# 24_-_HEADERS_UART.net
KiCad netlist of a schematic drawn in Altium Designer
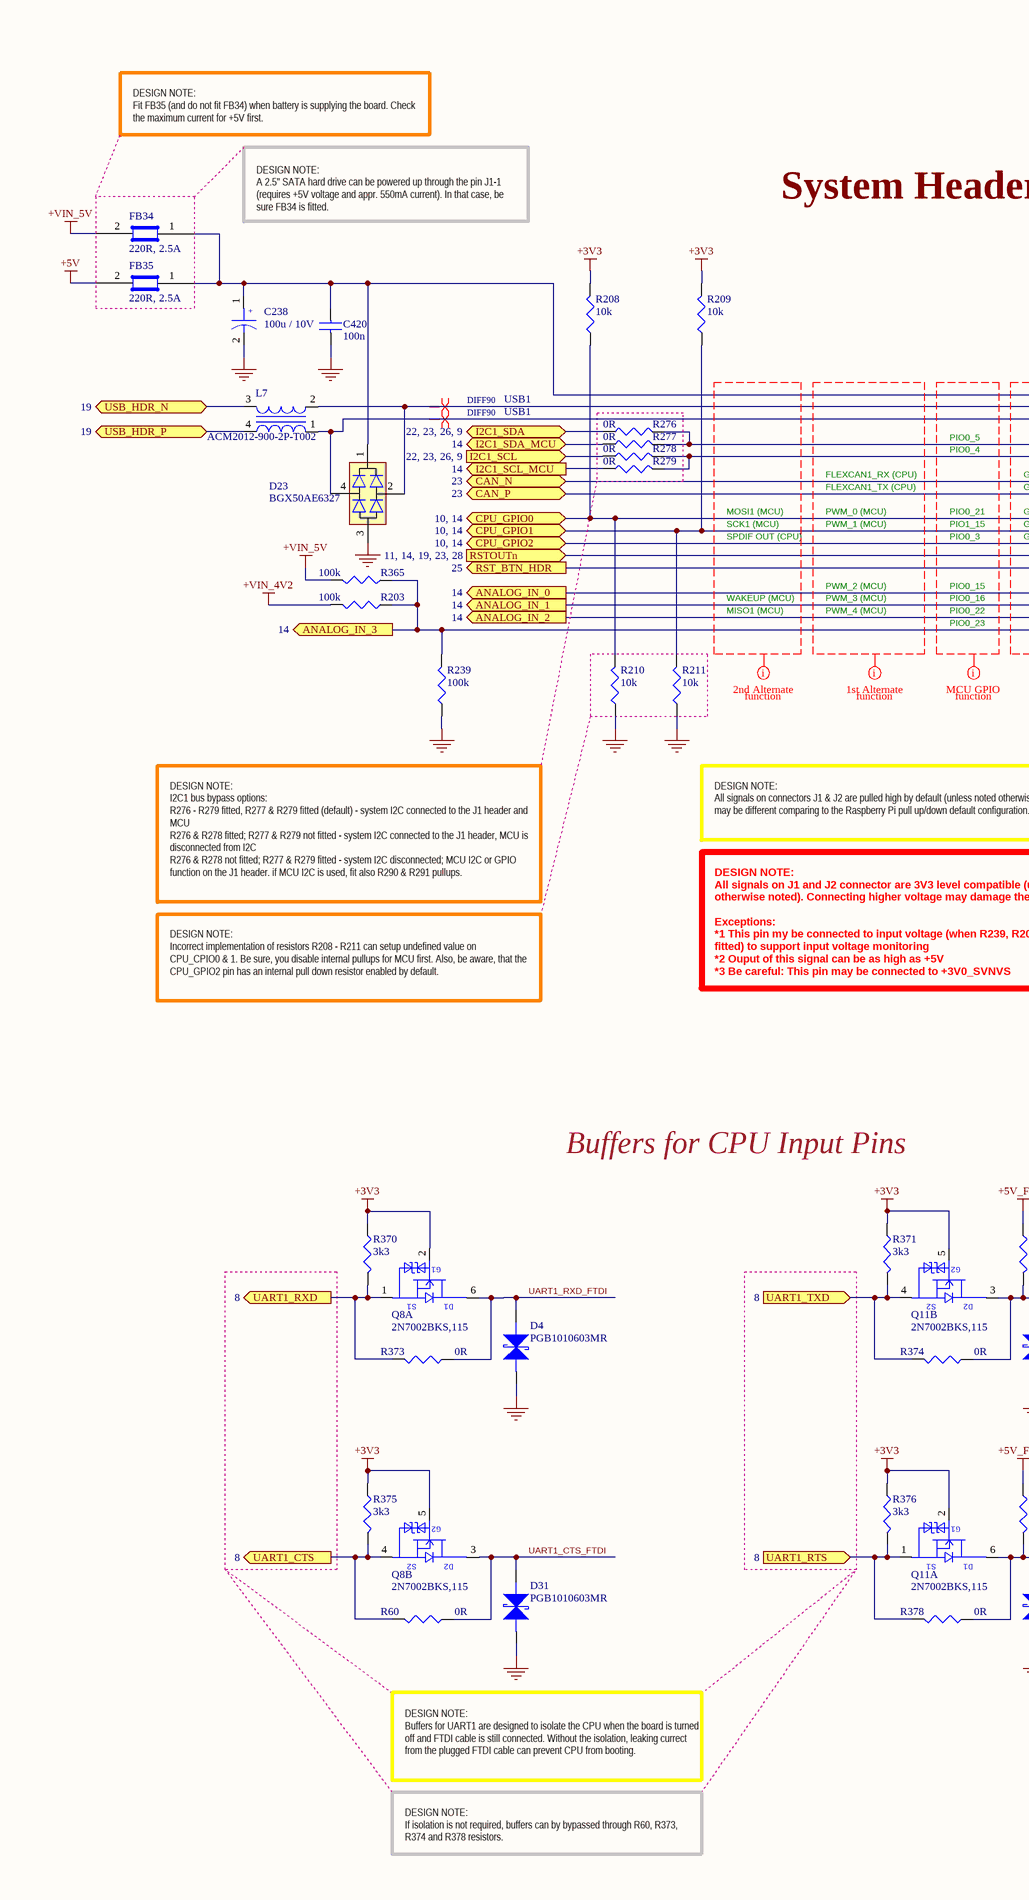
[diagram p0: [24] - HEADERS, UART.SchDoc, left]
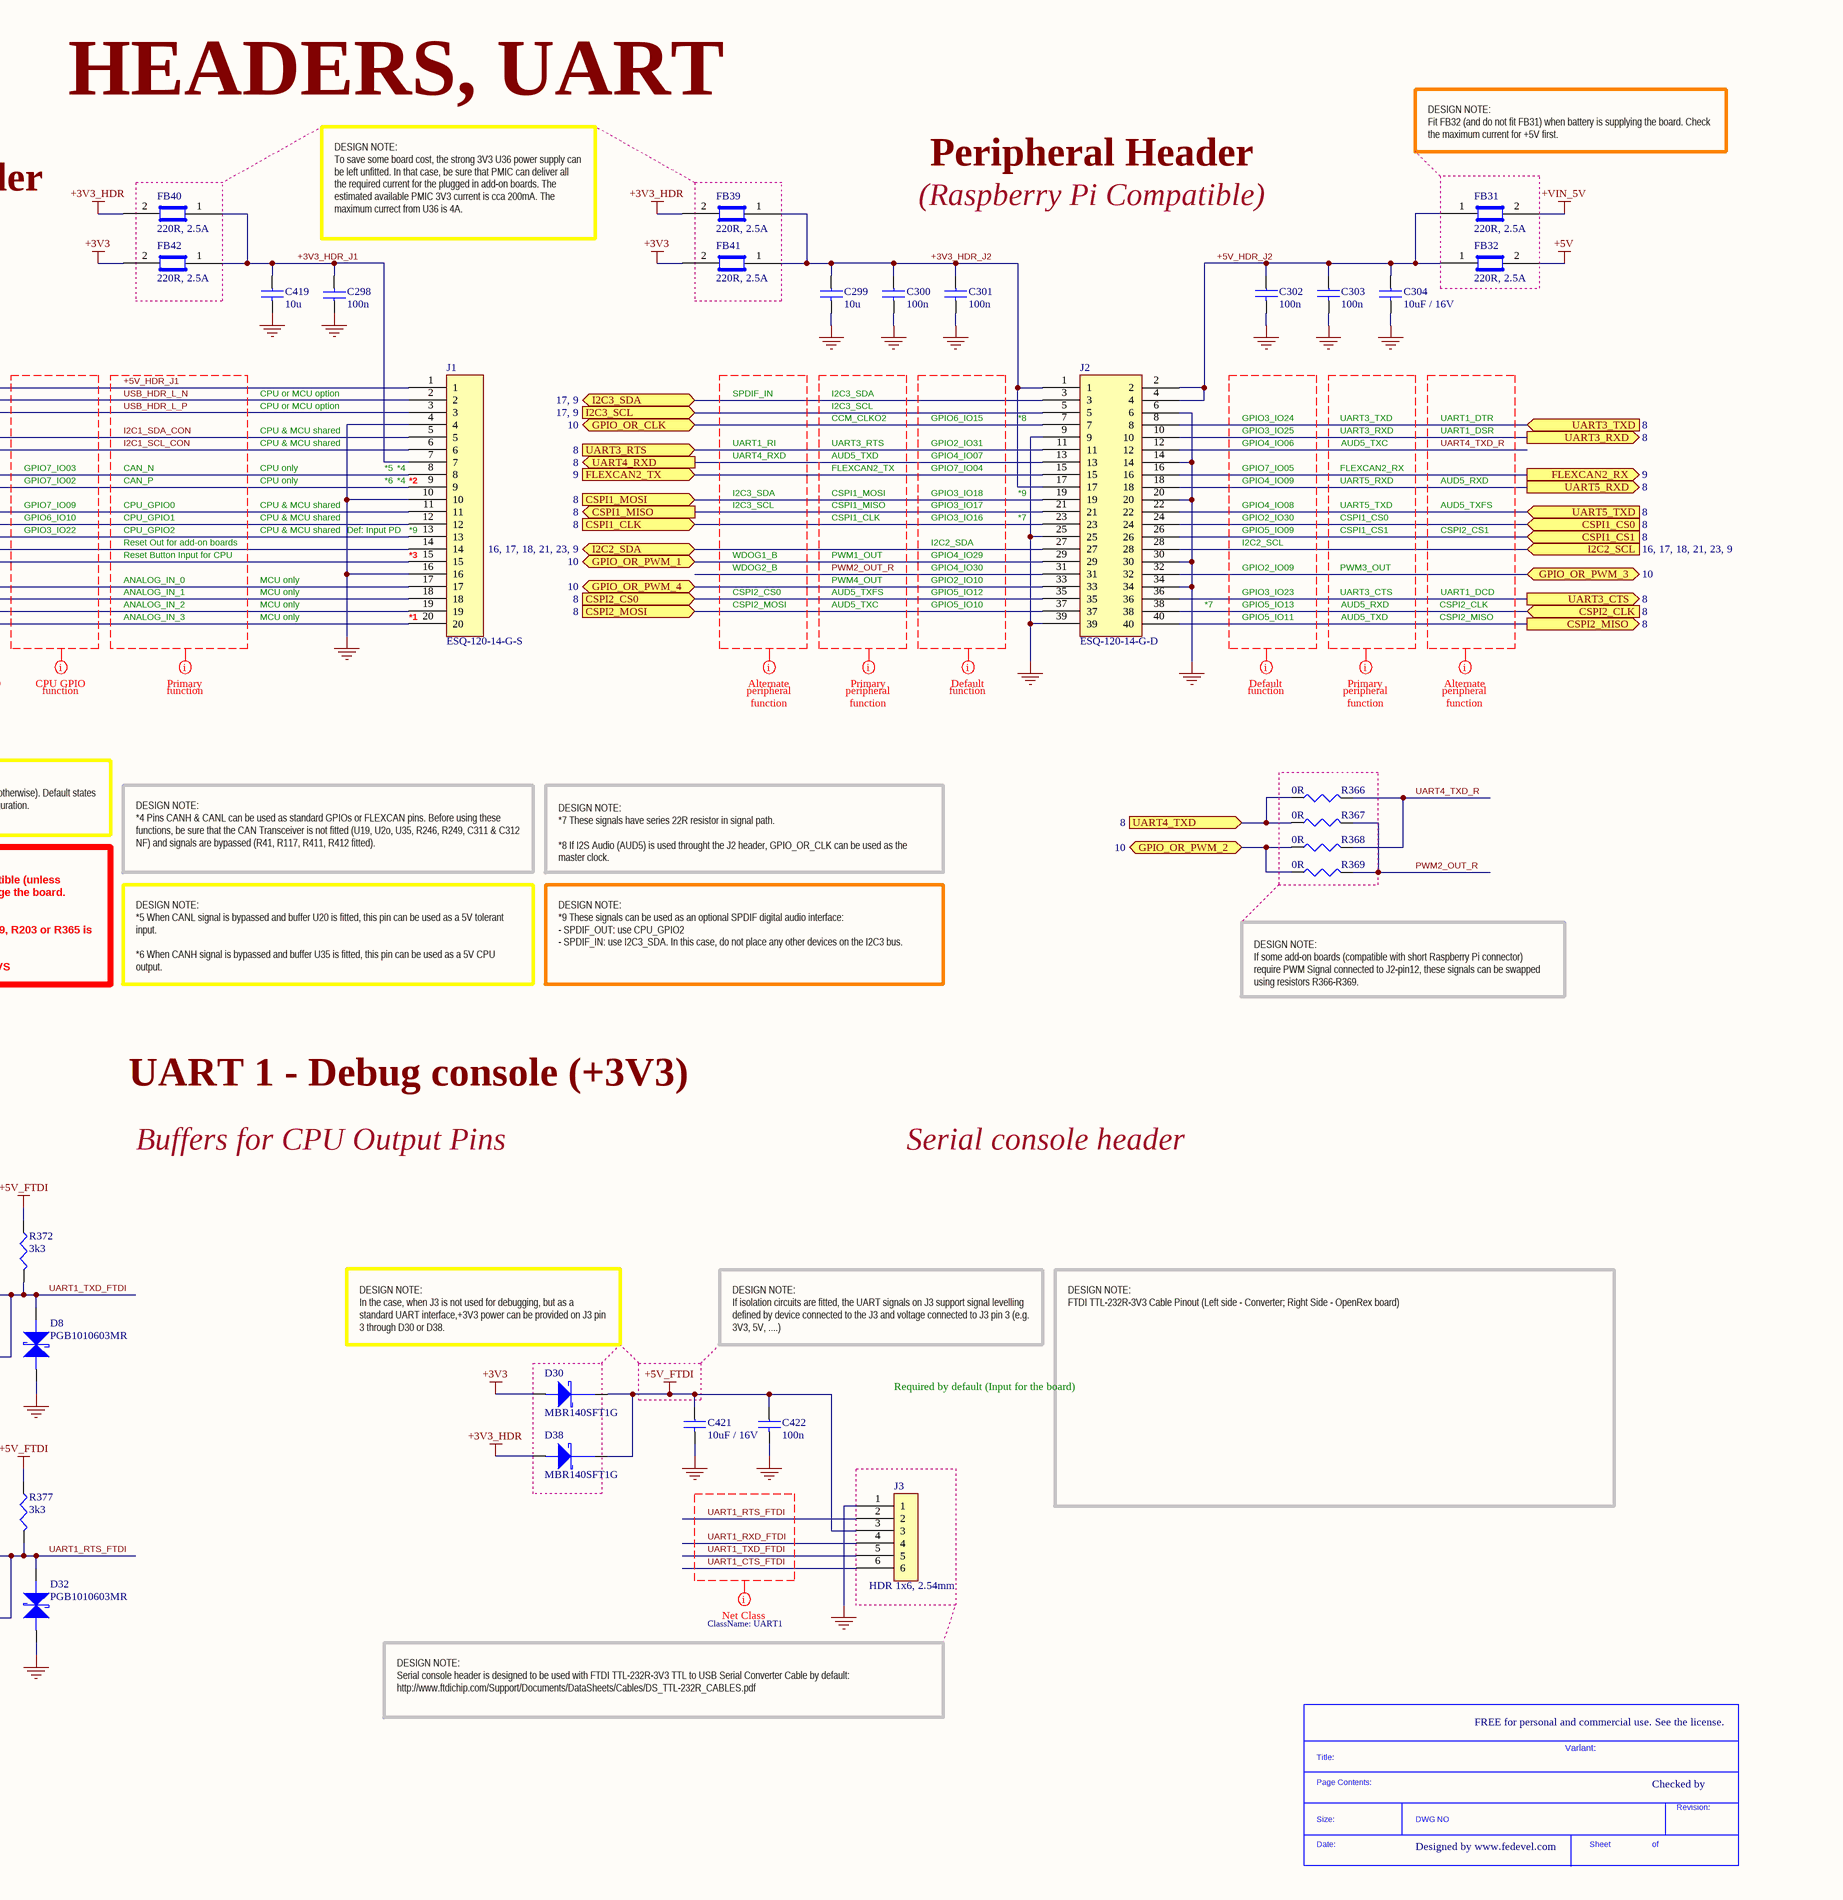
[diagram p1: [24] - HEADERS, UART.SchDoc, right]

(export (version "E")
  (design (tool "Eeschema 10.0.6"))
  (components
    (comp (ref "C238")
      (value "100u / 10V")
      (footprint "C2312")
      (description "CAP TANT 100UF 10V 10% 2312")
      (fields
        (field (name "MANUFACTURER") "AVX Corporation")
        (field (name "MANUFACTURER PART NUMBER") "TPSC107K010R0150")
        (field (name ".CREATOR") "MM")
        (field (name ".CHECKED PCB") "MM")
        (field (name ".CHECKED SCH") "MM")
      )
      (libsource (lib "Integrated_Library_FEDEVEL_APR_2015") (part "TPSC107K010R0150"))
    )
    (comp (ref "C298")
      (value "100n")
      (footprint "C0402")
      (description "CAP CER .10UF 50V X5R 10% 0402")
      (fields
        (field (name "MANUFACTURER") "TDK Corporation")
        (field (name "MANUFACTURER PART NUMBER") "C1005X5R1H104K")
      )
      (libsource (lib "Integrated_Library_FEDEVEL_APR_2015") (part "C1005X5R1H104K"))
    )
    (comp (ref "C299")
      (value "10u")
      (footprint "C0603")
      (description "CAP CER 10UF 6.3V X5R 20% 0603")
      (fields
        (field (name "MANUFACTURER") "TDK Corporation")
        (field (name "MANUFACTURER PART NUMBER") "C1608X5R0J106M")
      )
      (libsource (lib "Integrated_Library_FEDEVEL_APR_2015") (part "C1608X5R0J106M"))
    )
    (comp (ref "C300")
      (value "100n")
      (footprint "C0402")
      (description "CAP CER .10UF 50V X5R 10% 0402")
      (fields
        (field (name "MANUFACTURER") "TDK Corporation")
        (field (name "MANUFACTURER PART NUMBER") "C1005X5R1H104K")
      )
      (libsource (lib "Integrated_Library_FEDEVEL_APR_2015") (part "C1005X5R1H104K"))
    )
    (comp (ref "C301")
      (value "100n")
      (footprint "C0402")
      (description "CAP CER .10UF 50V X5R 10% 0402")
      (fields
        (field (name "MANUFACTURER") "TDK Corporation")
        (field (name "MANUFACTURER PART NUMBER") "C1005X5R1H104K")
      )
      (libsource (lib "Integrated_Library_FEDEVEL_APR_2015") (part "C1005X5R1H104K"))
    )
    (comp (ref "C302")
      (value "100n")
      (footprint "C0402")
      (description "CAP CER .10UF 50V X5R 10% 0402")
      (fields
        (field (name "MANUFACTURER") "TDK Corporation")
        (field (name "MANUFACTURER PART NUMBER") "C1005X5R1H104K")
      )
      (libsource (lib "Integrated_Library_FEDEVEL_APR_2015") (part "C1005X5R1H104K"))
    )
    (comp (ref "C303")
      (value "100n")
      (footprint "C0402")
      (description "CAP CER .10UF 50V X5R 10% 0402")
      (fields
        (field (name "MANUFACTURER") "TDK Corporation")
        (field (name "MANUFACTURER PART NUMBER") "C1005X5R1H104K")
      )
      (libsource (lib "Integrated_Library_FEDEVEL_APR_2015") (part "C1005X5R1H104K"))
    )
    (comp (ref "C304")
      (value "10uF / 16V")
      (footprint "C0805")
      (description "CAP CER 10UF 16V 20% X5R 0805")
      (fields
        (field (name "MANUFACTURER") "TDK Corporation")
        (field (name "MANUFACTURER PART NUMBER") "C2012X5R1C106M/1.25")
      )
      (libsource (lib "Integrated_Library_FEDEVEL_APR_2015") (part "C2012X5R1C106M"))
    )
    (comp (ref "C419")
      (value "10u")
      (footprint "C0603")
      (description "CAP CER 10UF 6.3V X5R 20% 0603")
      (fields
        (field (name "MANUFACTURER") "TDK Corporation")
        (field (name "MANUFACTURER PART NUMBER") "C1608X5R0J106M")
      )
      (libsource (lib "Integrated_Library_FEDEVEL_APR_2015") (part "C1608X5R0J106M"))
    )
    (comp (ref "C420")
      (value "100n")
      (footprint "C0402")
      (description "CAP CER .10UF 50V X5R 10% 0402")
      (fields
        (field (name "MANUFACTURER") "TDK Corporation")
        (field (name "MANUFACTURER PART NUMBER") "C1005X5R1H104K")
      )
      (libsource (lib "Integrated_Library_FEDEVEL_APR_2015") (part "C1005X5R1H104K"))
    )
    (comp (ref "C421")
      (value "10uF / 16V")
      (footprint "C0805")
      (description "CAP CER 10UF 16V 20% X5R 0805")
      (fields
        (field (name "MANUFACTURER") "TDK Corporation")
        (field (name "MANUFACTURER PART NUMBER") "C2012X5R1C106M/1.25")
      )
      (libsource (lib "Integrated_Library_FEDEVEL_APR_2015") (part "C2012X5R1C106M"))
    )
    (comp (ref "C422")
      (value "100n")
      (footprint "C0402")
      (description "CAP CER .10UF 50V X5R 10% 0402")
      (fields
        (field (name "MANUFACTURER") "TDK Corporation")
        (field (name "MANUFACTURER PART NUMBER") "C1005X5R1H104K")
      )
      (libsource (lib "Integrated_Library_FEDEVEL_APR_2015") (part "C1005X5R1H104K"))
    )
    (comp (ref "D4")
      (value "PGB1010603MR")
      (footprint "C0603")
      (description "SUPPRESSOR ESD 24VDC 0603 SMD")
      (fields (field (name "MANUFACTURER") "Littelfuse Inc") (field (name ".CREATOR") "MM"))
      (libsource (lib "Integrated_Library_FEDEVEL_APR_2015") (part "PGB1010603MR"))
    )
    (comp (ref "D8")
      (value "PGB1010603MR")
      (footprint "C0603")
      (description "SUPPRESSOR ESD 24VDC 0603 SMD")
      (fields (field (name "MANUFACTURER") "Littelfuse Inc") (field (name ".CREATOR") "MM"))
      (libsource (lib "Integrated_Library_FEDEVEL_APR_2015") (part "PGB1010603MR"))
    )
    (comp (ref "D23")
      (value "BGX50AE6327")
      (footprint "SOT143")
      (description "DIODE SWITCHING 50V SOT-143")
      (fields (field (name "MANUFACTURER") "Infineon Technologies"))
      (libsource (lib "Integrated_Library_FEDEVEL_APR_2015") (part "BGX50AE6327"))
    )
    (comp (ref "D30")
      (value "MBR140SFT1G")
      (footprint "SOD-123FL")
      (description "DIODE SCHOTTKY 40V 1A SOD123L")
      (fields
        (field (name "MANUFACTURER") "ON Semiconductor")
        (field (name ".CREATOR") "MM")
        (field (name ".CHECKED PCB") "MM")
        (field (name ".CHECKED SCH") "MM")
      )
      (libsource (lib "Integrated_Library_FEDEVEL_APR_2015") (part "MBR140SFT1G"))
    )
    (comp (ref "D31")
      (value "PGB1010603MR")
      (footprint "C0603")
      (description "SUPPRESSOR ESD 24VDC 0603 SMD")
      (fields (field (name "MANUFACTURER") "Littelfuse Inc") (field (name ".CREATOR") "MM"))
      (libsource (lib "Integrated_Library_FEDEVEL_APR_2015") (part "PGB1010603MR"))
    )
    (comp (ref "D32")
      (value "PGB1010603MR")
      (footprint "C0603")
      (description "SUPPRESSOR ESD 24VDC 0603 SMD")
      (fields (field (name "MANUFACTURER") "Littelfuse Inc") (field (name ".CREATOR") "MM"))
      (libsource (lib "Integrated_Library_FEDEVEL_APR_2015") (part "PGB1010603MR"))
    )
    (comp (ref "D38")
      (value "MBR140SFT1G")
      (footprint "SOD-123FL")
      (description "DIODE SCHOTTKY 40V 1A SOD123L")
      (fields
        (field (name "MANUFACTURER") "ON Semiconductor")
        (field (name ".CREATOR") "MM")
        (field (name ".CHECKED PCB") "MM")
        (field (name ".CHECKED SCH") "MM")
      )
      (libsource (lib "Integrated_Library_FEDEVEL_APR_2015") (part "MBR140SFT1G"))
    )
    (comp (ref "FB31")
      (value "220R, 2.5A")
      (footprint "C0603")
      (description "FERRITE CHIP 220 OHM 2500MA 0603")
      (fields
        (field (name "MANUFACTURER") "Murata Electronics North America")
        (field (name "MANUFACTURER PART NUMBER") "BLM18SG221TN1D")
      )
      (libsource (lib "Integrated_Library_FEDEVEL_APR_2015") (part "BLM18SG221TN1D"))
    )
    (comp (ref "FB32")
      (value "220R, 2.5A")
      (footprint "C0603")
      (description "FERRITE CHIP 220 OHM 2500MA 0603")
      (fields
        (field (name "MANUFACTURER") "Murata Electronics North America")
        (field (name "MANUFACTURER PART NUMBER") "BLM18SG221TN1D")
      )
      (libsource (lib "Integrated_Library_FEDEVEL_APR_2015") (part "BLM18SG221TN1D"))
    )
    (comp (ref "FB34")
      (value "220R, 2.5A")
      (footprint "C0603")
      (description "FERRITE CHIP 220 OHM 2500MA 0603")
      (fields
        (field (name "MANUFACTURER") "Murata Electronics North America")
        (field (name "MANUFACTURER PART NUMBER") "BLM18SG221TN1D")
      )
      (libsource (lib "Integrated_Library_FEDEVEL_APR_2015") (part "BLM18SG221TN1D"))
    )
    (comp (ref "FB35")
      (value "220R, 2.5A")
      (footprint "C0603")
      (description "FERRITE CHIP 220 OHM 2500MA 0603")
      (fields
        (field (name "MANUFACTURER") "Murata Electronics North America")
        (field (name "MANUFACTURER PART NUMBER") "BLM18SG221TN1D")
      )
      (libsource (lib "Integrated_Library_FEDEVEL_APR_2015") (part "BLM18SG221TN1D"))
    )
    (comp (ref "FB39")
      (value "220R, 2.5A")
      (footprint "C0603")
      (description "FERRITE CHIP 220 OHM 2500MA 0603")
      (fields
        (field (name "MANUFACTURER") "Murata Electronics North America")
        (field (name "MANUFACTURER PART NUMBER") "BLM18SG221TN1D")
      )
      (libsource (lib "Integrated_Library_FEDEVEL_APR_2015") (part "BLM18SG221TN1D"))
    )
    (comp (ref "FB40")
      (value "220R, 2.5A")
      (footprint "C0603")
      (description "FERRITE CHIP 220 OHM 2500MA 0603")
      (fields
        (field (name "MANUFACTURER") "Murata Electronics North America")
        (field (name "MANUFACTURER PART NUMBER") "BLM18SG221TN1D")
      )
      (libsource (lib "Integrated_Library_FEDEVEL_APR_2015") (part "BLM18SG221TN1D"))
    )
    (comp (ref "FB41")
      (value "220R, 2.5A")
      (footprint "C0603")
      (description "FERRITE CHIP 220 OHM 2500MA 0603")
      (fields
        (field (name "MANUFACTURER") "Murata Electronics North America")
        (field (name "MANUFACTURER PART NUMBER") "BLM18SG221TN1D")
      )
      (libsource (lib "Integrated_Library_FEDEVEL_APR_2015") (part "BLM18SG221TN1D"))
    )
    (comp (ref "FB42")
      (value "220R, 2.5A")
      (footprint "C0603")
      (description "FERRITE CHIP 220 OHM 2500MA 0603")
      (fields
        (field (name "MANUFACTURER") "Murata Electronics North America")
        (field (name "MANUFACTURER PART NUMBER") "BLM18SG221TN1D")
      )
      (libsource (lib "Integrated_Library_FEDEVEL_APR_2015") (part "BLM18SG221TN1D"))
    )
    (comp (ref "J1")
      (value "ESQ-120-14-G-S")
      (footprint "ESQ-120-14-G-S")
      (description "CONN RCPT 20POS .100\" DUAL GOLD")
      (fields
        (field (name "MANUFACTURER") "Samtec Inc.")
        (field (name ".CREATOR") "MM")
        (field (name ".CHECKED PCB") "MM, paper model not checked")
        (field (name ".CHECKED SCH") "MM")
      )
      (libsource (lib "Integrated_Library_FEDEVEL_APR_2015") (part "ESQ-120-14-G-S"))
    )
    (comp (ref "J2")
      (value "ESQ-120-14-G-D")
      (footprint "ESQ-120-14-G-D")
      (description "CONN RCPT 40POS .100\" DUAL GOLD")
      (fields
        (field (name "MANUFACTURER") "Samtec Inc.")
        (field (name ".CREATOR") "MM")
        (field (name ".CHECKED PCB") "MM")
        (field (name ".CHECKED SCH") "MM")
      )
      (libsource (lib "Integrated_Library_FEDEVEL_APR_2015") (part "ESQ-120-14-G-D"))
    )
    (comp (ref "J3")
      (value "HDR 1x6, 2.54mm")
      (footprint "Hdr_1x6_2.54mm")
      (description "CONN HEADER 6POS .100 STR 15AU")
      (fields
        (field (name "MANUFACTURER") "FCI")
        (field (name "MANUFACTURER PART NUMBER") "68001-206HLF")
        (field (name ".CREATOR") "MM")
        (field (name ".CHECKED PCB") "MM")
        (field (name ".CHECKED SCH") "MM")
      )
      (libsource (lib "Integrated_Library_FEDEVEL_APR_2015") (part "68001-206HLF"))
    )
    (comp (ref "L7")
      (value "ACM2012-900-2P-T002")
      (footprint "ACM2012")
      (description "CHOKE COMM MODE 90 OHM .4A SMD")
      (fields (field (name "MANUFACTURER") "TDK Corporation") (field (name "TOLERANCE") "±1%"))
      (libsource (lib "Integrated_Library_FEDEVEL_APR_2015") (part "ACM2012-900-2P-T002"))
    )
    (comp (ref "Q8")
      (value "2N7002BKS,115")
      (footprint "SOT363")
      (description "MOSFET 2N-CH 60V 0.3A 6TSSOP")
      (fields
        (field (name "MANUFACTURER") "NXP Semiconductors")
        (field (name ".CREATOR") "MM")
        (field (name ".CHECKED SCH") "MM")
        (field (name ".CHECKED PCB") "MM")
      )
      (libsource (lib "Integrated_Library_FEDEVEL_APR_2015") (part "2N7002BKS,115"))
    )
    (comp (ref "Q11")
      (value "2N7002BKS,115")
      (footprint "SOT363")
      (description "MOSFET 2N-CH 60V 0.3A 6TSSOP")
      (fields
        (field (name "MANUFACTURER") "NXP Semiconductors")
        (field (name ".CREATOR") "MM")
        (field (name ".CHECKED SCH") "MM")
        (field (name ".CHECKED PCB") "MM")
      )
      (libsource (lib "Integrated_Library_FEDEVEL_APR_2015") (part "2N7002BKS,115"))
    )
    (comp (ref "R60")
      (value "0R")
      (footprint "R0402")
      (description "RES 0.0 OHM 1/16W 0402 SMD")
      (fields
        (field (name "MANUFACTURER") "Yageo")
        (field (name "MANUFACTURER PART NUMBER") "RC0402JR-070RL")
      )
      (libsource (lib "Integrated_Library_FEDEVEL_APR_2015") (part "RC0402JR-070RL"))
    )
    (comp (ref "R203")
      (value "100k")
      (footprint "R0402")
      (description "RES 100K OHM 1/16W 1% 0402 SMD")
      (fields
        (field (name "MANUFACTURER") "Stackpole Electronics Inc")
        (field (name "MANUFACTURER PART NUMBER") "RMCF0402FT100K")
      )
      (libsource (lib "Integrated_Library_FEDEVEL_APR_2015") (part "RMCF0402FT100K"))
    )
    (comp (ref "R208")
      (value "10k")
      (footprint "R0402")
      (description "RES 10.0K OHM 1/16W 1% 0402 SMD")
      (fields
        (field (name "MANUFACTURER") "Yageo")
        (field (name "MANUFACTURER PART NUMBER") "RC0402FR-0710KL")
      )
      (libsource (lib "Integrated_Library_FEDEVEL_APR_2015") (part "RC0402FR-0710KL"))
    )
    (comp (ref "R209")
      (value "10k")
      (footprint "R0402")
      (description "RES 10.0K OHM 1/16W 1% 0402 SMD")
      (fields
        (field (name "MANUFACTURER") "Yageo")
        (field (name "MANUFACTURER PART NUMBER") "RC0402FR-0710KL")
      )
      (libsource (lib "Integrated_Library_FEDEVEL_APR_2015") (part "RC0402FR-0710KL"))
    )
    (comp (ref "R210")
      (value "10k")
      (footprint "R0402")
      (description "RES 10.0K OHM 1/16W 1% 0402 SMD")
      (fields
        (field (name "MANUFACTURER") "Yageo")
        (field (name "MANUFACTURER PART NUMBER") "RC0402FR-0710KL")
      )
      (libsource (lib "Integrated_Library_FEDEVEL_APR_2015") (part "RC0402FR-0710KL"))
    )
    (comp (ref "R211")
      (value "10k")
      (footprint "R0402")
      (description "RES 10.0K OHM 1/16W 1% 0402 SMD")
      (fields
        (field (name "MANUFACTURER") "Yageo")
        (field (name "MANUFACTURER PART NUMBER") "RC0402FR-0710KL")
      )
      (libsource (lib "Integrated_Library_FEDEVEL_APR_2015") (part "RC0402FR-0710KL"))
    )
    (comp (ref "R239")
      (value "100k")
      (footprint "R0402")
      (description "RES 100K OHM 1/16W 1% 0402 SMD")
      (fields
        (field (name "MANUFACTURER") "Stackpole Electronics Inc")
        (field (name "MANUFACTURER PART NUMBER") "RMCF0402FT100K")
      )
      (libsource (lib "Integrated_Library_FEDEVEL_APR_2015") (part "RMCF0402FT100K"))
    )
    (comp (ref "R276")
      (value "0R")
      (footprint "R0402")
      (description "RES 0.0 OHM 1/16W 0402 SMD")
      (fields
        (field (name "MANUFACTURER") "Yageo")
        (field (name "MANUFACTURER PART NUMBER") "RC0402JR-070RL")
      )
      (libsource (lib "Integrated_Library_FEDEVEL_APR_2015") (part "RC0402JR-070RL"))
    )
    (comp (ref "R277")
      (value "0R")
      (footprint "R0402")
      (description "RES 0.0 OHM 1/16W 0402 SMD")
      (fields
        (field (name "MANUFACTURER") "Yageo")
        (field (name "MANUFACTURER PART NUMBER") "RC0402JR-070RL")
      )
      (libsource (lib "Integrated_Library_FEDEVEL_APR_2015") (part "RC0402JR-070RL"))
    )
    (comp (ref "R278")
      (value "0R")
      (footprint "R0402")
      (description "RES 0.0 OHM 1/16W 0402 SMD")
      (fields
        (field (name "MANUFACTURER") "Yageo")
        (field (name "MANUFACTURER PART NUMBER") "RC0402JR-070RL")
      )
      (libsource (lib "Integrated_Library_FEDEVEL_APR_2015") (part "RC0402JR-070RL"))
    )
    (comp (ref "R279")
      (value "0R")
      (footprint "R0402")
      (description "RES 0.0 OHM 1/16W 0402 SMD")
      (fields
        (field (name "MANUFACTURER") "Yageo")
        (field (name "MANUFACTURER PART NUMBER") "RC0402JR-070RL")
      )
      (libsource (lib "Integrated_Library_FEDEVEL_APR_2015") (part "RC0402JR-070RL"))
    )
    (comp (ref "R365")
      (value "100k")
      (footprint "R0402")
      (description "RES 100K OHM 1/16W 1% 0402 SMD")
      (fields
        (field (name "MANUFACTURER") "Stackpole Electronics Inc")
        (field (name "MANUFACTURER PART NUMBER") "RMCF0402FT100K")
      )
      (libsource (lib "Integrated_Library_FEDEVEL_APR_2015") (part "RMCF0402FT100K"))
    )
    (comp (ref "R366")
      (value "0R")
      (footprint "R0402")
      (description "RES 0.0 OHM 1/16W 0402 SMD")
      (fields
        (field (name "MANUFACTURER") "Yageo")
        (field (name "MANUFACTURER PART NUMBER") "RC0402JR-070RL")
      )
      (libsource (lib "Integrated_Library_FEDEVEL_APR_2015") (part "RC0402JR-070RL"))
    )
    (comp (ref "R367")
      (value "0R")
      (footprint "R0402")
      (description "RES 0.0 OHM 1/16W 0402 SMD")
      (fields
        (field (name "MANUFACTURER") "Yageo")
        (field (name "MANUFACTURER PART NUMBER") "RC0402JR-070RL")
      )
      (libsource (lib "Integrated_Library_FEDEVEL_APR_2015") (part "RC0402JR-070RL"))
    )
    (comp (ref "R368")
      (value "0R")
      (footprint "R0402")
      (description "RES 0.0 OHM 1/16W 0402 SMD")
      (fields
        (field (name "MANUFACTURER") "Yageo")
        (field (name "MANUFACTURER PART NUMBER") "RC0402JR-070RL")
      )
      (libsource (lib "Integrated_Library_FEDEVEL_APR_2015") (part "RC0402JR-070RL"))
    )
    (comp (ref "R369")
      (value "0R")
      (footprint "R0402")
      (description "RES 0.0 OHM 1/16W 0402 SMD")
      (fields
        (field (name "MANUFACTURER") "Yageo")
        (field (name "MANUFACTURER PART NUMBER") "RC0402JR-070RL")
      )
      (libsource (lib "Integrated_Library_FEDEVEL_APR_2015") (part "RC0402JR-070RL"))
    )
    (comp (ref "R370")
      (value "3k3")
      (footprint "R0402")
      (description "RES 3.30K OHM 1/16W 1% 0402 SMD")
      (fields
        (field (name "MANUFACTURER") "Yageo")
        (field (name "MANUFACTURER PART NUMBER") "RC0402FR-073K3L")
      )
      (libsource (lib "Integrated_Library_FEDEVEL_APR_2015") (part "RC0402FR-073K3L"))
    )
    (comp (ref "R371")
      (value "3k3")
      (footprint "R0402")
      (description "RES 3.30K OHM 1/16W 1% 0402 SMD")
      (fields
        (field (name "MANUFACTURER") "Yageo")
        (field (name "MANUFACTURER PART NUMBER") "RC0402FR-073K3L")
      )
      (libsource (lib "Integrated_Library_FEDEVEL_APR_2015") (part "RC0402FR-073K3L"))
    )
    (comp (ref "R372")
      (value "3k3")
      (footprint "R0402")
      (description "RES 3.30K OHM 1/16W 1% 0402 SMD")
      (fields
        (field (name "MANUFACTURER") "Yageo")
        (field (name "MANUFACTURER PART NUMBER") "RC0402FR-073K3L")
      )
      (libsource (lib "Integrated_Library_FEDEVEL_APR_2015") (part "RC0402FR-073K3L"))
    )
    (comp (ref "R373")
      (value "0R")
      (footprint "R0402")
      (description "RES 0.0 OHM 1/16W 0402 SMD")
      (fields
        (field (name "MANUFACTURER") "Yageo")
        (field (name "MANUFACTURER PART NUMBER") "RC0402JR-070RL")
      )
      (libsource (lib "Integrated_Library_FEDEVEL_APR_2015") (part "RC0402JR-070RL"))
    )
    (comp (ref "R374")
      (value "0R")
      (footprint "R0402")
      (description "RES 0.0 OHM 1/16W 0402 SMD")
      (fields
        (field (name "MANUFACTURER") "Yageo")
        (field (name "MANUFACTURER PART NUMBER") "RC0402JR-070RL")
      )
      (libsource (lib "Integrated_Library_FEDEVEL_APR_2015") (part "RC0402JR-070RL"))
    )
    (comp (ref "R375")
      (value "3k3")
      (footprint "R0402")
      (description "RES 3.30K OHM 1/16W 1% 0402 SMD")
      (fields
        (field (name "MANUFACTURER") "Yageo")
        (field (name "MANUFACTURER PART NUMBER") "RC0402FR-073K3L")
      )
      (libsource (lib "Integrated_Library_FEDEVEL_APR_2015") (part "RC0402FR-073K3L"))
    )
    (comp (ref "R376")
      (value "3k3")
      (footprint "R0402")
      (description "RES 3.30K OHM 1/16W 1% 0402 SMD")
      (fields
        (field (name "MANUFACTURER") "Yageo")
        (field (name "MANUFACTURER PART NUMBER") "RC0402FR-073K3L")
      )
      (libsource (lib "Integrated_Library_FEDEVEL_APR_2015") (part "RC0402FR-073K3L"))
    )
    (comp (ref "R377")
      (value "3k3")
      (footprint "R0402")
      (description "RES 3.30K OHM 1/16W 1% 0402 SMD")
      (fields
        (field (name "MANUFACTURER") "Yageo")
        (field (name "MANUFACTURER PART NUMBER") "RC0402FR-073K3L")
      )
      (libsource (lib "Integrated_Library_FEDEVEL_APR_2015") (part "RC0402FR-073K3L"))
    )
    (comp (ref "R378")
      (value "0R")
      (footprint "R0402")
      (description "RES 0.0 OHM 1/16W 0402 SMD")
      (fields
        (field (name "MANUFACTURER") "Yageo")
        (field (name "MANUFACTURER PART NUMBER") "RC0402JR-070RL")
      )
      (libsource (lib "Integrated_Library_FEDEVEL_APR_2015") (part "RC0402JR-070RL"))
    )
  )
  (nets
    (net (code "1") (name "+3V3") (class "Default")
      (node (ref "D30") (pin "2") (pinfunction "Anode_2") (pintype "passive"))
      (node (ref "FB41") (pin "2") (pinfunction "2_2") (pintype "passive"))
      (node (ref "FB42") (pin "2") (pinfunction "2_2") (pintype "passive"))
      (node (ref "Q11") (pin "2") (pinfunction "GATE1_2") (pintype "passive"))
      (node (ref "Q11") (pin "5") (pinfunction "GATE2_5") (pintype "passive"))
      (node (ref "Q8") (pin "2") (pinfunction "GATE1_2") (pintype "passive"))
      (node (ref "Q8") (pin "5") (pinfunction "GATE2_5") (pintype "passive"))
      (node (ref "R208") (pin "2") (pinfunction "2_2") (pintype "passive"))
      (node (ref "R209") (pin "2") (pinfunction "2_2") (pintype "passive"))
      (node (ref "R370") (pin "2") (pinfunction "2_2") (pintype "passive"))
      (node (ref "R371") (pin "2") (pinfunction "2_2") (pintype "passive"))
      (node (ref "R375") (pin "2") (pinfunction "2_2") (pintype "passive"))
      (node (ref "R376") (pin "2") (pinfunction "2_2") (pintype "passive"))
    )
    (net (code "2") (name "+3V3_HDR") (class "Default")
      (node (ref "D38") (pin "2") (pinfunction "Anode_2") (pintype "passive"))
      (node (ref "FB39") (pin "2") (pinfunction "2_2") (pintype "passive"))
      (node (ref "FB40") (pin "2") (pinfunction "2_2") (pintype "passive"))
    )
    (net (code "3") (name "+5V") (class "Default")
      (node (ref "FB32") (pin "2") (pinfunction "2_2") (pintype "passive"))
      (node (ref "FB35") (pin "2") (pinfunction "2_2") (pintype "passive"))
    )
    (net (code "4") (name "+5V_FTDI") (class "Default")
      (node (ref "C421") (pin "1") (pinfunction "1_1") (pintype "passive"))
      (node (ref "C422") (pin "1") (pinfunction "1_1") (pintype "passive"))
      (node (ref "D30") (pin "1") (pinfunction "Cathode_1") (pintype "passive"))
      (node (ref "D38") (pin "1") (pinfunction "Cathode_1") (pintype "passive"))
      (node (ref "J3") (pin "3") (pinfunction "3_3") (pintype "passive"))
      (node (ref "R372") (pin "2") (pinfunction "2_2") (pintype "passive"))
      (node (ref "R377") (pin "2") (pinfunction "2_2") (pintype "passive"))
    )
    (net (code "5") (name "+VIN_4V2") (class "Default")
      (node (ref "R203") (pin "2") (pinfunction "2_2") (pintype "passive"))
    )
    (net (code "6") (name "+VIN_5V") (class "Default")
      (node (ref "FB31") (pin "2") (pinfunction "2_2") (pintype "passive"))
      (node (ref "FB34") (pin "2") (pinfunction "2_2") (pintype "passive"))
      (node (ref "R365") (pin "2") (pinfunction "2_2") (pintype "passive"))
    )
    (net (code "7") (name "/+3V3_HDR_J1") (class "Default")
      (node (ref "C298") (pin "2") (pinfunction "2_2") (pintype "passive"))
      (node (ref "C419") (pin "1") (pinfunction "1_1") (pintype "passive"))
      (node (ref "FB40") (pin "1") (pinfunction "1_1") (pintype "passive"))
      (node (ref "FB42") (pin "1") (pinfunction "1_1") (pintype "passive"))
      (node (ref "J1") (pin "7") (pinfunction "7_7") (pintype "passive"))
    )
    (net (code "8") (name "/+3V3_HDR_J2") (class "Default")
      (node (ref "C299") (pin "1") (pinfunction "1_1") (pintype "passive"))
      (node (ref "C300") (pin "1") (pinfunction "1_1") (pintype "passive"))
      (node (ref "C301") (pin "1") (pinfunction "1_1") (pintype "passive"))
      (node (ref "FB39") (pin "1") (pinfunction "1_1") (pintype "passive"))
      (node (ref "FB41") (pin "1") (pinfunction "1_1") (pintype "passive"))
      (node (ref "J2") (pin "1") (pinfunction "1_1") (pintype "passive"))
      (node (ref "J2") (pin "17") (pinfunction "17_17") (pintype "passive"))
    )
    (net (code "9") (name "/+5V_HDR_J1") (class "Default")
      (node (ref "C238") (pin "1") (pinfunction "1_1") (pintype "passive"))
      (node (ref "C420") (pin "1") (pinfunction "1_1") (pintype "passive"))
      (node (ref "D23") (pin "1") (pinfunction "1_1") (pintype "passive"))
      (node (ref "FB34") (pin "1") (pinfunction "1_1") (pintype "passive"))
      (node (ref "FB35") (pin "1") (pinfunction "1_1") (pintype "passive"))
      (node (ref "J1") (pin "1") (pinfunction "1_1") (pintype "passive"))
    )
    (net (code "10") (name "/+5V_HDR_J2") (class "Default")
      (node (ref "C302") (pin "1") (pinfunction "1_1") (pintype "passive"))
      (node (ref "C303") (pin "1") (pinfunction "1_1") (pintype "passive"))
      (node (ref "C304") (pin "1") (pinfunction "1_1") (pintype "passive"))
      (node (ref "FB31") (pin "1") (pinfunction "1_1") (pintype "passive"))
      (node (ref "FB32") (pin "1") (pinfunction "1_1") (pintype "passive"))
      (node (ref "J2") (pin "2") (pinfunction "2_2") (pintype "passive"))
      (node (ref "J2") (pin "4") (pinfunction "4_4") (pintype "passive"))
    )
    (net (code "11") (name "/ANALOG_IN_0") (class "Default")
      (node (ref "J1") (pin "17") (pinfunction "17_17") (pintype "passive"))
    )
    (net (code "12") (name "/ANALOG_IN_1") (class "Default")
      (node (ref "J1") (pin "18") (pinfunction "18_18") (pintype "passive"))
    )
    (net (code "13") (name "/ANALOG_IN_2") (class "Default")
      (node (ref "J1") (pin "19") (pinfunction "19_19") (pintype "passive"))
    )
    (net (code "14") (name "/ANALOG_IN_3") (class "Default")
      (node (ref "J1") (pin "20") (pinfunction "20_20") (pintype "passive"))
      (node (ref "R203") (pin "1") (pinfunction "1_1") (pintype "passive"))
      (node (ref "R239") (pin "2") (pinfunction "2_2") (pintype "passive"))
      (node (ref "R365") (pin "1") (pinfunction "1_1") (pintype "passive"))
    )
    (net (code "15") (name "/CAN_N") (class "Default")
      (node (ref "J1") (pin "8") (pinfunction "8_8") (pintype "passive"))
    )
    (net (code "16") (name "/CAN_P") (class "Default")
      (node (ref "J1") (pin "9") (pinfunction "9_9") (pintype "passive"))
    )
    (net (code "17") (name "/CPU_GPIO0") (class "Default")
      (node (ref "J1") (pin "11") (pinfunction "11_11") (pintype "passive"))
      (node (ref "R208") (pin "1") (pinfunction "1_1") (pintype "passive"))
      (node (ref "R210") (pin "2") (pinfunction "2_2") (pintype "passive"))
    )
    (net (code "18") (name "/CPU_GPIO1") (class "Default")
      (node (ref "J1") (pin "12") (pinfunction "12_12") (pintype "passive"))
      (node (ref "R209") (pin "1") (pinfunction "1_1") (pintype "passive"))
      (node (ref "R211") (pin "2") (pinfunction "2_2") (pintype "passive"))
    )
    (net (code "19") (name "/CPU_GPIO2") (class "Default")
      (node (ref "J1") (pin "13") (pinfunction "13_13") (pintype "passive"))
    )
    (net (code "20") (name "/CSPI1_CLK") (class "Default")
      (node (ref "J2") (pin "23") (pinfunction "23_23") (pintype "passive"))
    )
    (net (code "21") (name "/CSPI1_CS0") (class "Default")
      (node (ref "J2") (pin "24") (pinfunction "24_24") (pintype "passive"))
    )
    (net (code "22") (name "/CSPI1_CS1") (class "Default")
      (node (ref "J2") (pin "26") (pinfunction "26_26") (pintype "passive"))
    )
    (net (code "23") (name "/CSPI1_MISO") (class "Default")
      (node (ref "J2") (pin "21") (pinfunction "21_21") (pintype "passive"))
    )
    (net (code "24") (name "/CSPI1_MOSI") (class "Default")
      (node (ref "J2") (pin "19") (pinfunction "19_19") (pintype "passive"))
    )
    (net (code "25") (name "/CSPI2_CLK") (class "Default")
      (node (ref "J2") (pin "38") (pinfunction "38_38") (pintype "passive"))
    )
    (net (code "26") (name "/CSPI2_CS0") (class "Default")
      (node (ref "J2") (pin "35") (pinfunction "35_35") (pintype "passive"))
    )
    (net (code "27") (name "/CSPI2_MISO") (class "Default")
      (node (ref "J2") (pin "40") (pinfunction "40_40") (pintype "passive"))
    )
    (net (code "28") (name "/CSPI2_MOSI") (class "Default")
      (node (ref "J2") (pin "37") (pinfunction "37_37") (pintype "passive"))
    )
    (net (code "29") (name "/FLEXCAN2_RX") (class "Default")
      (node (ref "J2") (pin "16") (pinfunction "16_16") (pintype "passive"))
    )
    (net (code "30") (name "/FLEXCAN2_TX") (class "Default")
      (node (ref "J2") (pin "15") (pinfunction "15_15") (pintype "passive"))
    )
    (net (code "31") (name "/GPIO_OR_CLK") (class "Default")
      (node (ref "J2") (pin "7") (pinfunction "7_7") (pintype "passive"))
    )
    (net (code "32") (name "/GPIO_OR_PWM_1") (class "Default")
      (node (ref "J2") (pin "29") (pinfunction "29_29") (pintype "passive"))
    )
    (net (code "33") (name "/GPIO_OR_PWM_2") (class "Default")
      (node (ref "R368") (pin "1") (pinfunction "1_1") (pintype "passive"))
      (node (ref "R369") (pin "1") (pinfunction "1_1") (pintype "passive"))
    )
    (net (code "34") (name "/GPIO_OR_PWM_3") (class "Default")
      (node (ref "J2") (pin "32") (pinfunction "32_32") (pintype "passive"))
    )
    (net (code "35") (name "/GPIO_OR_PWM_4") (class "Default")
      (node (ref "J2") (pin "33") (pinfunction "33_33") (pintype "passive"))
    )
    (net (code "36") (name "/I2C1_SCL") (class "Default")
      (node (ref "R278") (pin "1") (pinfunction "1_1") (pintype "passive"))
    )
    (net (code "37") (name "/I2C1_SCL_CON") (class "Default")
      (node (ref "J1") (pin "6") (pinfunction "6_6") (pintype "passive"))
      (node (ref "R278") (pin "2") (pinfunction "2_2") (pintype "passive"))
      (node (ref "R279") (pin "2") (pinfunction "2_2") (pintype "passive"))
    )
    (net (code "38") (name "/I2C1_SCL_MCU") (class "Default")
      (node (ref "R279") (pin "1") (pinfunction "1_1") (pintype "passive"))
    )
    (net (code "39") (name "/I2C1_SDA") (class "Default")
      (node (ref "R276") (pin "1") (pinfunction "1_1") (pintype "passive"))
    )
    (net (code "40") (name "/I2C1_SDA_CON") (class "Default")
      (node (ref "J1") (pin "5") (pinfunction "5_5") (pintype "passive"))
      (node (ref "R276") (pin "2") (pinfunction "2_2") (pintype "passive"))
      (node (ref "R277") (pin "2") (pinfunction "2_2") (pintype "passive"))
    )
    (net (code "41") (name "/I2C1_SDA_MCU") (class "Default")
      (node (ref "R277") (pin "1") (pinfunction "1_1") (pintype "passive"))
    )
    (net (code "42") (name "/I2C2_SCL") (class "Default")
      (node (ref "J2") (pin "28") (pinfunction "28_28") (pintype "passive"))
    )
    (net (code "43") (name "/I2C2_SDA") (class "Default")
      (node (ref "J2") (pin "27") (pinfunction "27_27") (pintype "passive"))
    )
    (net (code "44") (name "/I2C3_SCL") (class "Default")
      (node (ref "J2") (pin "5") (pinfunction "5_5") (pintype "passive"))
    )
    (net (code "45") (name "/I2C3_SDA") (class "Default")
      (node (ref "J2") (pin "3") (pinfunction "3_3") (pintype "passive"))
    )
    (net (code "46") (name "/PWM2_OUT_R") (class "Default")
      (node (ref "J2") (pin "31") (pinfunction "31_31") (pintype "passive"))
      (node (ref "R367") (pin "2") (pinfunction "2_2") (pintype "passive"))
      (node (ref "R369") (pin "2") (pinfunction "2_2") (pintype "passive"))
    )
    (net (code "47") (name "/RSTOUTn") (class "Default")
      (node (ref "J1") (pin "14") (pinfunction "14_14") (pintype "passive"))
    )
    (net (code "48") (name "/RST_BTN_HDR") (class "Default")
      (node (ref "J1") (pin "15") (pinfunction "15_15") (pintype "passive"))
    )
    (net (code "49") (name "/UART1_CTS") (class "Default")
      (node (ref "Q8") (pin "4") (pinfunction "SOURCE2_4") (pintype "passive"))
      (node (ref "R375") (pin "1") (pinfunction "1_1") (pintype "passive"))
      (node (ref "R60") (pin "1") (pinfunction "1_1") (pintype "passive"))
    )
    (net (code "50") (name "/UART1_CTS_FTDI") (class "Default")
      (node (ref "D31") (pin "1") (pinfunction "1_1") (pintype "passive"))
      (node (ref "J3") (pin "6") (pinfunction "6_6") (pintype "passive"))
      (node (ref "Q8") (pin "3") (pinfunction "DRAIN2_3") (pintype "passive"))
      (node (ref "R60") (pin "2") (pinfunction "2_2") (pintype "passive"))
    )
    (net (code "51") (name "/UART1_RTS") (class "Default")
      (node (ref "Q11") (pin "1") (pinfunction "SOURCE1_1") (pintype "passive"))
      (node (ref "R376") (pin "1") (pinfunction "1_1") (pintype "passive"))
      (node (ref "R378") (pin "1") (pinfunction "1_1") (pintype "passive"))
    )
    (net (code "52") (name "/UART1_RTS_FTDI") (class "Default")
      (node (ref "D32") (pin "1") (pinfunction "1_1") (pintype "passive"))
      (node (ref "J3") (pin "2") (pinfunction "2_2") (pintype "passive"))
      (node (ref "Q11") (pin "6") (pinfunction "DRAIN1_6") (pintype "passive"))
      (node (ref "R377") (pin "1") (pinfunction "1_1") (pintype "passive"))
      (node (ref "R378") (pin "2") (pinfunction "2_2") (pintype "passive"))
    )
    (net (code "53") (name "/UART1_RXD") (class "Default")
      (node (ref "Q8") (pin "1") (pinfunction "SOURCE1_1") (pintype "passive"))
      (node (ref "R370") (pin "1") (pinfunction "1_1") (pintype "passive"))
      (node (ref "R373") (pin "1") (pinfunction "1_1") (pintype "passive"))
    )
    (net (code "54") (name "/UART1_RXD_FTDI") (class "Default")
      (node (ref "D4") (pin "1") (pinfunction "1_1") (pintype "passive"))
      (node (ref "J3") (pin "4") (pinfunction "4_4") (pintype "passive"))
      (node (ref "Q8") (pin "6") (pinfunction "DRAIN1_6") (pintype "passive"))
      (node (ref "R373") (pin "2") (pinfunction "2_2") (pintype "passive"))
    )
    (net (code "55") (name "/UART1_TXD") (class "Default")
      (node (ref "Q11") (pin "4") (pinfunction "SOURCE2_4") (pintype "passive"))
      (node (ref "R371") (pin "1") (pinfunction "1_1") (pintype "passive"))
      (node (ref "R374") (pin "1") (pinfunction "1_1") (pintype "passive"))
    )
    (net (code "56") (name "/UART1_TXD_FTDI") (class "Default")
      (node (ref "D8") (pin "1") (pinfunction "1_1") (pintype "passive"))
      (node (ref "J3") (pin "5") (pinfunction "5_5") (pintype "passive"))
      (node (ref "Q11") (pin "3") (pinfunction "DRAIN2_3") (pintype "passive"))
      (node (ref "R372") (pin "1") (pinfunction "1_1") (pintype "passive"))
      (node (ref "R374") (pin "2") (pinfunction "2_2") (pintype "passive"))
    )
    (net (code "57") (name "/UART3_CTS") (class "Default")
      (node (ref "J2") (pin "36") (pinfunction "36_36") (pintype "passive"))
    )
    (net (code "58") (name "/UART3_RTS") (class "Default")
      (node (ref "J2") (pin "11") (pinfunction "11_11") (pintype "passive"))
    )
    (net (code "59") (name "/UART3_RXD") (class "Default")
      (node (ref "J2") (pin "10") (pinfunction "10_10") (pintype "passive"))
    )
    (net (code "60") (name "/UART3_TXD") (class "Default")
      (node (ref "J2") (pin "8") (pinfunction "8_8") (pintype "passive"))
    )
    (net (code "61") (name "/UART4_RXD") (class "Default")
      (node (ref "J2") (pin "13") (pinfunction "13_13") (pintype "passive"))
    )
    (net (code "62") (name "/UART4_TXD") (class "Default")
      (node (ref "R366") (pin "1") (pinfunction "1_1") (pintype "passive"))
      (node (ref "R367") (pin "1") (pinfunction "1_1") (pintype "passive"))
    )
    (net (code "63") (name "/UART4_TXD_R") (class "Default")
      (node (ref "J2") (pin "12") (pinfunction "12_12") (pintype "passive"))
      (node (ref "R366") (pin "2") (pinfunction "2_2") (pintype "passive"))
      (node (ref "R368") (pin "2") (pinfunction "2_2") (pintype "passive"))
    )
    (net (code "64") (name "/UART5_RXD") (class "Default")
      (node (ref "J2") (pin "18") (pinfunction "18_18") (pintype "passive"))
    )
    (net (code "65") (name "/UART5_TXD") (class "Default")
      (node (ref "J2") (pin "22") (pinfunction "22_22") (pintype "passive"))
    )
    (net (code "66") (name "/USB_HDR_L_N") (class "Default")
      (node (ref "D23") (pin "2") (pinfunction "2_2") (pintype "passive"))
      (node (ref "J1") (pin "2") (pinfunction "2_2") (pintype "passive"))
      (node (ref "L7") (pin "2") (pinfunction "2_2") (pintype "passive"))
    )
    (net (code "67") (name "/USB_HDR_L_P") (class "Default")
      (node (ref "D23") (pin "4") (pinfunction "4_4") (pintype "passive"))
      (node (ref "J1") (pin "3") (pinfunction "3_3") (pintype "passive"))
      (node (ref "L7") (pin "1") (pinfunction "1_1") (pintype "passive"))
    )
    (net (code "68") (name "/USB_HDR_N") (class "Default")
      (node (ref "L7") (pin "3") (pinfunction "3_3") (pintype "passive"))
    )
    (net (code "69") (name "/USB_HDR_P") (class "Default")
      (node (ref "L7") (pin "4") (pinfunction "4_4") (pintype "passive"))
    )
    (net (code "70") (name "GND") (class "Default")
      (node (ref "C238") (pin "2") (pinfunction "2_2") (pintype "passive"))
      (node (ref "C298") (pin "1") (pinfunction "1_1") (pintype "passive"))
      (node (ref "C299") (pin "2") (pinfunction "2_2") (pintype "passive"))
      (node (ref "C300") (pin "2") (pinfunction "2_2") (pintype "passive"))
      (node (ref "C301") (pin "2") (pinfunction "2_2") (pintype "passive"))
      (node (ref "C302") (pin "2") (pinfunction "2_2") (pintype "passive"))
      (node (ref "C303") (pin "2") (pinfunction "2_2") (pintype "passive"))
      (node (ref "C304") (pin "2") (pinfunction "2_2") (pintype "passive"))
      (node (ref "C419") (pin "2") (pinfunction "2_2") (pintype "passive"))
      (node (ref "C420") (pin "2") (pinfunction "2_2") (pintype "passive"))
      (node (ref "C421") (pin "2") (pinfunction "2_2") (pintype "passive"))
      (node (ref "C422") (pin "2") (pinfunction "2_2") (pintype "passive"))
      (node (ref "D23") (pin "3") (pinfunction "3_3") (pintype "passive"))
      (node (ref "D31") (pin "2") (pinfunction "2_2") (pintype "passive"))
      (node (ref "D32") (pin "2") (pinfunction "2_2") (pintype "passive"))
      (node (ref "D4") (pin "2") (pinfunction "2_2") (pintype "passive"))
      (node (ref "D8") (pin "2") (pinfunction "2_2") (pintype "passive"))
      (node (ref "J1") (pin "10") (pinfunction "10_10") (pintype "passive"))
      (node (ref "J1") (pin "16") (pinfunction "16_16") (pintype "passive"))
      (node (ref "J1") (pin "4") (pinfunction "4_4") (pintype "passive"))
      (node (ref "J2") (pin "14") (pinfunction "14_14") (pintype "passive"))
      (node (ref "J2") (pin "20") (pinfunction "20_20") (pintype "passive"))
      (node (ref "J2") (pin "25") (pinfunction "25_25") (pintype "passive"))
      (node (ref "J2") (pin "30") (pinfunction "30_30") (pintype "passive"))
      (node (ref "J2") (pin "34") (pinfunction "34_34") (pintype "passive"))
      (node (ref "J2") (pin "39") (pinfunction "39_39") (pintype "passive"))
      (node (ref "J2") (pin "6") (pinfunction "6_6") (pintype "passive"))
      (node (ref "J2") (pin "9") (pinfunction "9_9") (pintype "passive"))
      (node (ref "J3") (pin "1") (pinfunction "1_1") (pintype "passive"))
      (node (ref "R210") (pin "1") (pinfunction "1_1") (pintype "passive"))
      (node (ref "R211") (pin "1") (pinfunction "1_1") (pintype "passive"))
      (node (ref "R239") (pin "1") (pinfunction "1_1") (pintype "passive"))
    )
  )
)
